# MainSchPBv2.net
KiCad netlist of a schematic drawn in Altium Designer
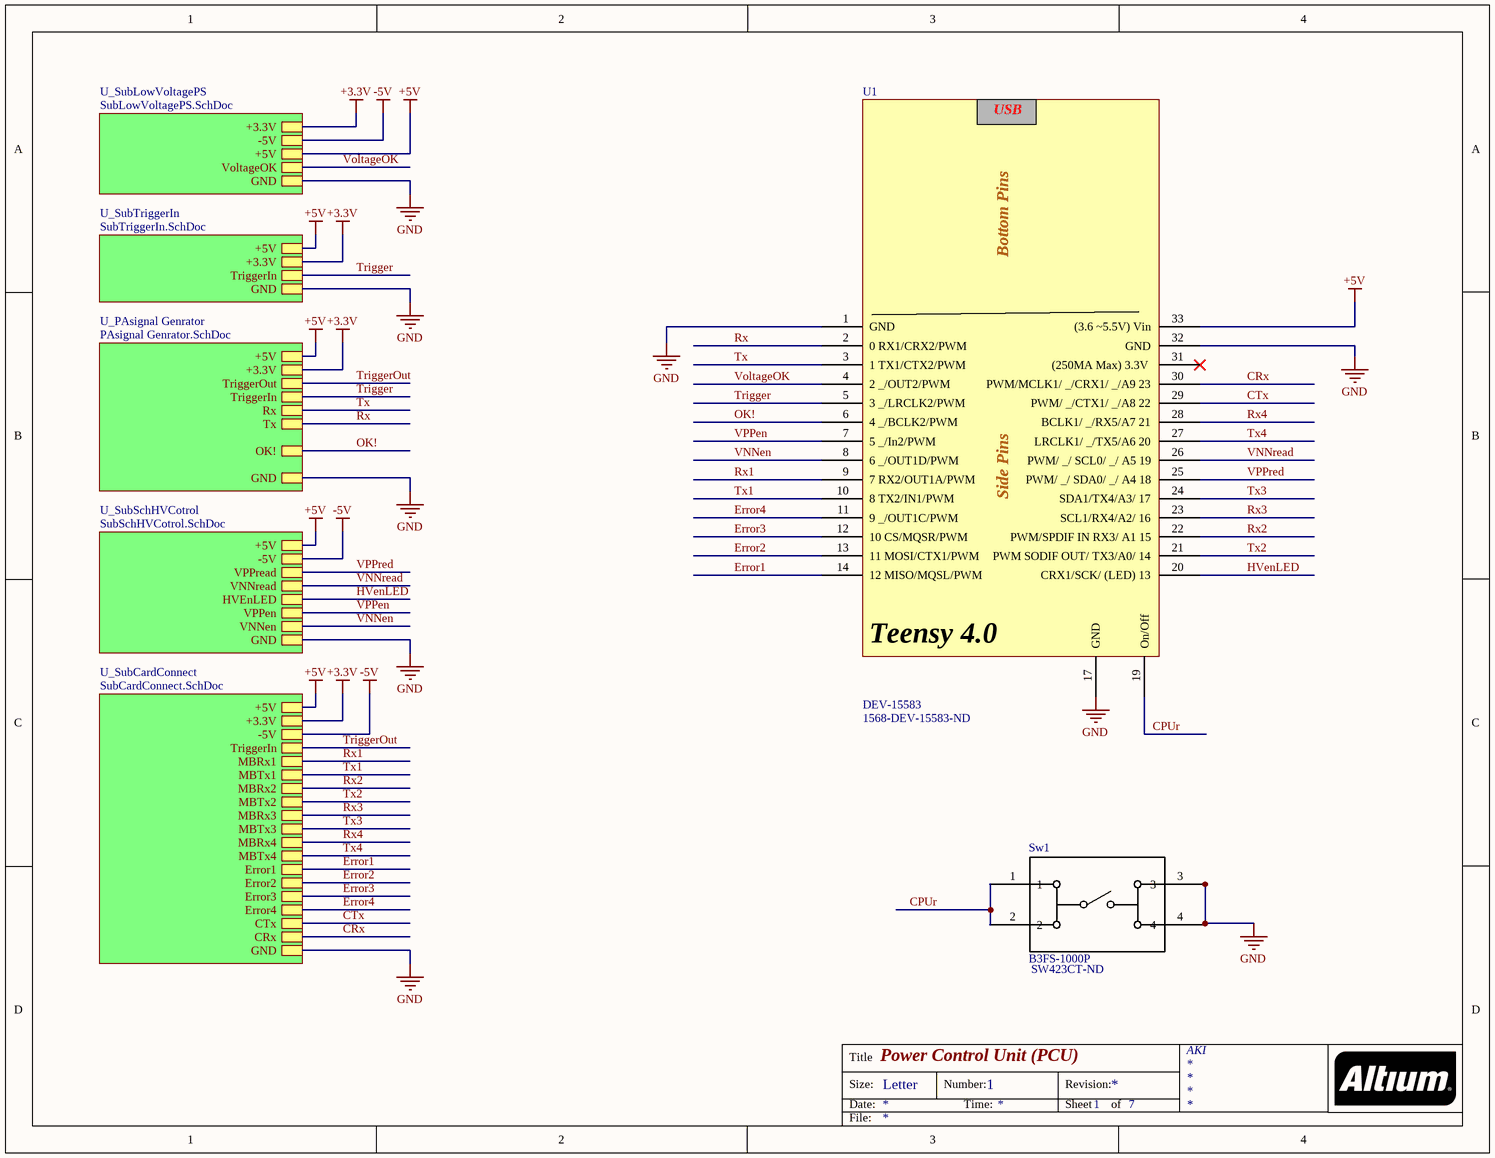
[diagram p0: MainSchPBv2.SchDoc]

(export (version "E")
  (design (tool "Eeschema 10.0.6"))
  (components
    (comp (ref "Sw1")
      (value "B3FS-1000P")
      (footprint "B3FS-1000P")
      (description "Tactile Switch SPST-NO Top Actuated Surface Mount")
      (fields (field (name "SUPPLIER PART NUMBER 1") "SW423CT-ND"))
      (libsource (lib "Afshin Library") (part "B3FS-1000P"))
    )
    (comp (ref "U1")
      (value "DEV-15583")
      (footprint "Teensy 4.0sideOnly")
      (fields (field (name "SUPPLIER PART NUMBER 1") "1568-DEV-15583-ND"))
      (libsource (lib "Afshin Library") (part "Teensy 4.0_SideOnly"))
    )
  )
  (nets
    (net (code "2") (name "+5V") (class "Default")
      (node (ref "U1") (pin "33") (pinfunction "(3.6_~5.5V)_Vin_33") (pintype "passive"))
    )
    (net (code "4") (name "/CPUr") (class "Default")
      (node (ref "Sw1") (pin "1") (pinfunction "1_1") (pintype "passive"))
      (node (ref "Sw1") (pin "2") (pinfunction "2_2") (pintype "passive"))
      (node (ref "U1") (pin "19") (pinfunction "On/Off_19") (pintype "passive"))
    )
    (net (code "5") (name "/CRx") (class "Default")
      (node (ref "U1") (pin "30") (pinfunction "PWM/MCLK1/__/CRX1/__/A9_23_30") (pintype "passive"))
    )
    (net (code "6") (name "/CTx") (class "Default")
      (node (ref "U1") (pin "29") (pinfunction "PWM/__/CTX1/__/A8_22_29") (pintype "passive"))
    )
    (net (code "7") (name "/Error1") (class "Default")
      (node (ref "U1") (pin "14") (pinfunction "12_MISO/MQSL/PWM_14") (pintype "passive"))
    )
    (net (code "8") (name "/Error2") (class "Default")
      (node (ref "U1") (pin "13") (pinfunction "11_MOSI/CTX1/PWM_13") (pintype "passive"))
    )
    (net (code "9") (name "/Error3") (class "Default")
      (node (ref "U1") (pin "12") (pinfunction "10_CS/MQSR/PWM_12") (pintype "passive"))
    )
    (net (code "10") (name "/Error4") (class "Default")
      (node (ref "U1") (pin "11") (pinfunction "9__/OUT1C/PWM_11") (pintype "passive"))
    )
    (net (code "11") (name "/HVenLED") (class "Default")
      (node (ref "U1") (pin "20") (pinfunction "CRX1/SCK/_(LED)_13_20") (pintype "passive"))
    )
    (net (code "12") (name "/OK!") (class "Default")
      (node (ref "U1") (pin "6") (pinfunction "4__/BCLK2/PWM_6") (pintype "passive"))
    )
    (net (code "13") (name "/Rx") (class "Default")
      (node (ref "U1") (pin "2") (pinfunction "0_RX1/CRX2/PWM_2") (pintype "passive"))
    )
    (net (code "14") (name "/Rx1") (class "Default")
      (node (ref "U1") (pin "9") (pinfunction "7_RX2/OUT1A/PWM_9") (pintype "passive"))
    )
    (net (code "15") (name "/Rx2") (class "Default")
      (node (ref "U1") (pin "22") (pinfunction "PWM/SPDIF_IN_RX3/_A1_15_22") (pintype "passive"))
    )
    (net (code "16") (name "/Rx3") (class "Default")
      (node (ref "U1") (pin "23") (pinfunction "SCL1/RX4/A2/_16_23") (pintype "passive"))
    )
    (net (code "17") (name "/Rx4") (class "Default")
      (node (ref "U1") (pin "28") (pinfunction "BCLK1/__/RX5/A7_21_28") (pintype "passive"))
    )
    (net (code "18") (name "/Trigger") (class "Default")
      (node (ref "U1") (pin "5") (pinfunction "3__/LRCLK2/PWM_5") (pintype "passive"))
    )
    (net (code "20") (name "/Tx") (class "Default")
      (node (ref "U1") (pin "3") (pinfunction "1_TX1/CTX2/PWM_3") (pintype "passive"))
    )
    (net (code "21") (name "/Tx1") (class "Default")
      (node (ref "U1") (pin "10") (pinfunction "8_TX2/IN1/PWM_10") (pintype "passive"))
    )
    (net (code "22") (name "/Tx2") (class "Default")
      (node (ref "U1") (pin "21") (pinfunction "PWM_SODIF_OUT/_TX3/A0/_14_21") (pintype "passive"))
    )
    (net (code "23") (name "/Tx3") (class "Default")
      (node (ref "U1") (pin "24") (pinfunction "SDA1/TX4/A3/_17_24") (pintype "passive"))
    )
    (net (code "24") (name "/Tx4") (class "Default")
      (node (ref "U1") (pin "27") (pinfunction "LRCLK1/__/TX5/A6_20_27") (pintype "passive"))
    )
    (net (code "25") (name "/VNNen") (class "Default")
      (node (ref "U1") (pin "8") (pinfunction "6__/OUT1D/PWM_8") (pintype "passive"))
    )
    (net (code "26") (name "/VNNread") (class "Default")
      (node (ref "U1") (pin "26") (pinfunction "PWM/__/_SCL0/__/_A5_19_26") (pintype "passive"))
    )
    (net (code "27") (name "/VPPen") (class "Default")
      (node (ref "U1") (pin "7") (pinfunction "5__/In2/PWM_7") (pintype "passive"))
    )
    (net (code "28") (name "/VPPred") (class "Default")
      (node (ref "U1") (pin "25") (pinfunction "PWM/__/_SDA0/__/_A4_18_25") (pintype "passive"))
    )
    (net (code "29") (name "/VoltageOK") (class "Default")
      (node (ref "U1") (pin "4") (pinfunction "2__/OUT2/PWM_4") (pintype "passive"))
    )
    (net (code "30") (name "GND") (class "Default")
      (node (ref "Sw1") (pin "3") (pinfunction "3_3") (pintype "passive"))
      (node (ref "Sw1") (pin "4") (pinfunction "4_4") (pintype "passive"))
      (node (ref "U1") (pin "1") (pinfunction "GND_1") (pintype "passive"))
      (node (ref "U1") (pin "17") (pinfunction "GND_17") (pintype "passive"))
      (node (ref "U1") (pin "32") (pinfunction "GND_32") (pintype "passive"))
    )
    (net (code "31") (name "unconnected-(U1-(250MA_Max)_3.3V-Pad31)") (class "Default")
      (node (ref "U1") (pin "31") (pinfunction "(250MA_Max)_3.3V_31") (pintype "passive+no_connect"))
    )
  )
)
